# TMR_MAGSAT.net
KiCad netlist of a schematic drawn in Altium Designer
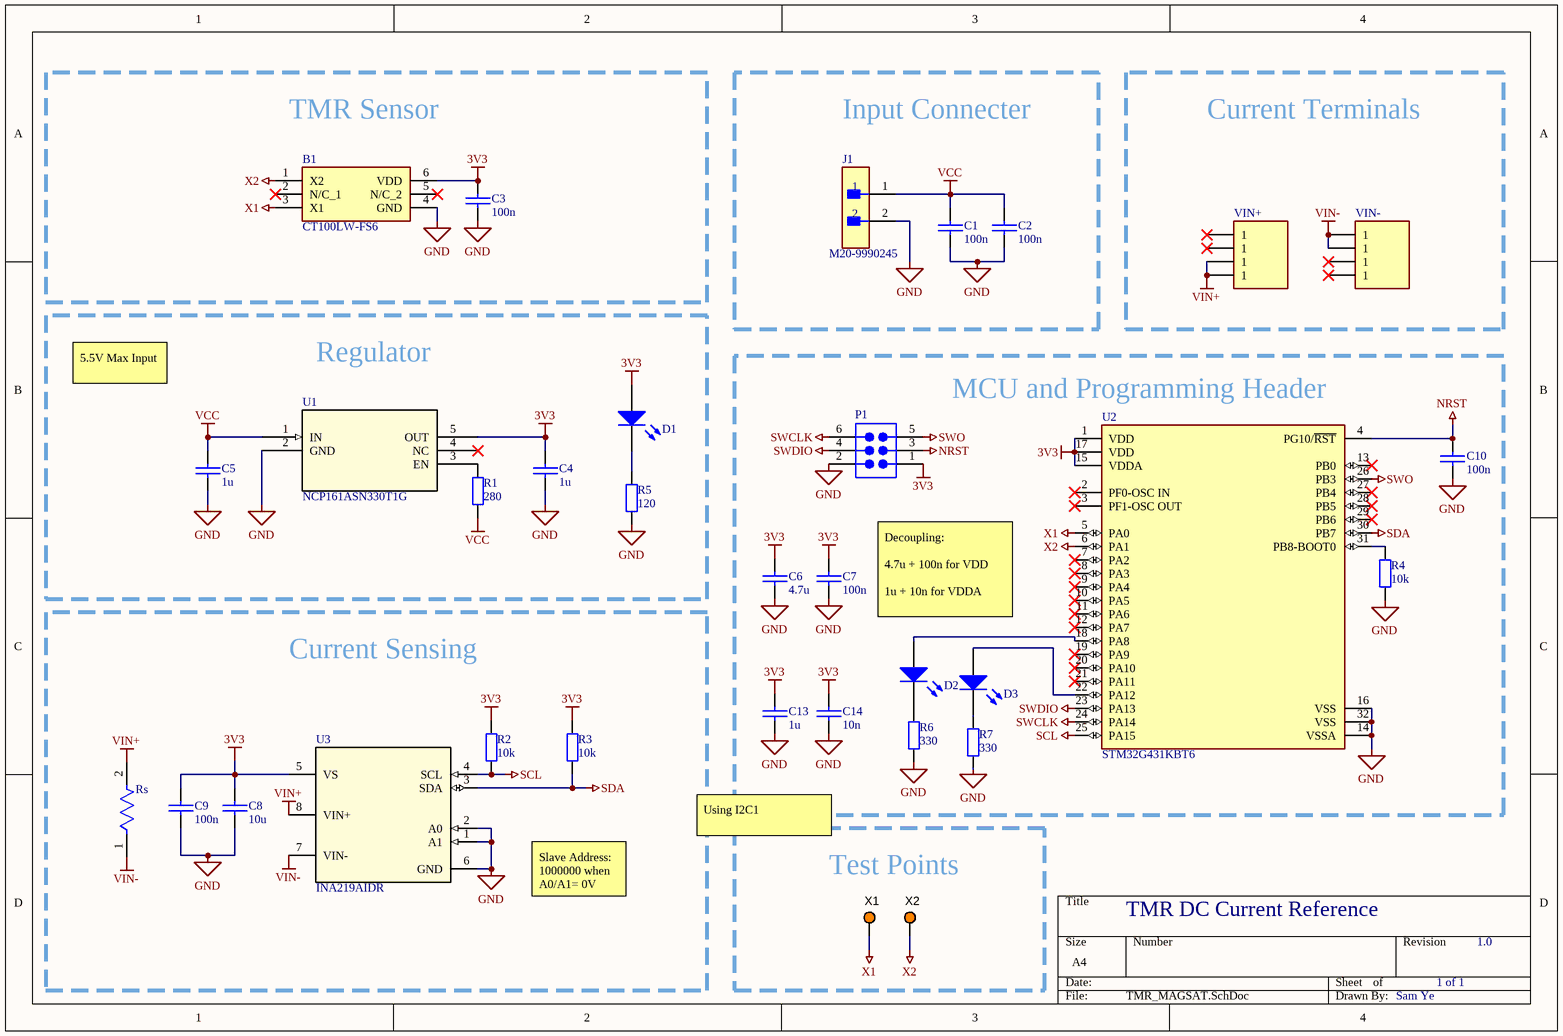
[diagram p0: TMR_MAGSAT.SchDoc]

(export (version "E")
  (design (tool "Eeschema 10.0.6"))
  (components
    (comp (ref "B1")
      (value "CT100LW-FS6")
      (footprint "SOT95P280X135-6N")
      (libsource (lib "CT100LW-FS6") (part "CT100LW-FS6"))
    )
    (comp (ref "C1")
      (value "100n")
      (footprint "0805 CAP")
      (description "SMT ceramic capacitor 0805 size")
      (libsource (lib "EE209_SchLib") (part "CerCap_SMT_0805"))
    )
    (comp (ref "C2")
      (value "100n")
      (footprint "0805 CAP")
      (description "SMT ceramic capacitor 0805 size")
      (libsource (lib "EE209_SchLib") (part "CerCap_SMT_0805"))
    )
    (comp (ref "C3")
      (value "100n")
      (footprint "0805 CAP")
      (description "SMT ceramic capacitor 0805 size")
      (libsource (lib "EE209_SchLib") (part "CerCap_SMT_0805"))
    )
    (comp (ref "C4")
      (value "1u")
      (footprint "0805 CAP")
      (description "SMT ceramic capacitor 0805 size")
      (libsource (lib "EE209_SchLib") (part "CerCap_SMT_0805"))
    )
    (comp (ref "C5")
      (value "1u")
      (footprint "0805 CAP")
      (description "SMT ceramic capacitor 0805 size")
      (libsource (lib "EE209_SchLib") (part "CerCap_SMT_0805"))
    )
    (comp (ref "C6")
      (value "4.7u")
      (footprint "0805 CAP")
      (description "SMT ceramic capacitor 0805 size")
      (libsource (lib "EE209_SchLib") (part "CerCap_SMT_0805"))
    )
    (comp (ref "C7")
      (value "100n")
      (footprint "0805 CAP")
      (description "SMT ceramic capacitor 0805 size")
      (libsource (lib "EE209_SchLib") (part "CerCap_SMT_0805"))
    )
    (comp (ref "C8")
      (value "10u")
      (footprint "0805 CAP")
      (description "SMT ceramic capacitor 0805 size")
      (libsource (lib "EE209_SchLib") (part "CerCap_SMT_0805"))
    )
    (comp (ref "C9")
      (value "100n")
      (footprint "0805 CAP")
      (description "SMT ceramic capacitor 0805 size")
      (libsource (lib "EE209_SchLib") (part "CerCap_SMT_0805"))
    )
    (comp (ref "C10")
      (value "100n")
      (footprint "0805 CAP")
      (description "SMT ceramic capacitor 0805 size")
      (libsource (lib "EE209_SchLib") (part "CerCap_SMT_0805"))
    )
    (comp (ref "C13")
      (value "1u")
      (footprint "0805 CAP")
      (description "SMT ceramic capacitor 0805 size")
      (libsource (lib "EE209_SchLib") (part "CerCap_SMT_0805"))
    )
    (comp (ref "C14")
      (value "10n")
      (footprint "0805 CAP")
      (description "SMT ceramic capacitor 0805 size")
      (libsource (lib "EE209_SchLib") (part "CerCap_SMT_0805"))
    )
    (comp (ref "D1")
      (value "LTST-C170KGKT")
      (footprint "0805 LED")
      (description "SMT LED 0805 size")
      (fields (field (name "MANUFACTURER") "Lite-On Inc."))
      (libsource (lib "EE209_SchLib") (part "LED_SMT_0805"))
    )
    (comp (ref "D2")
      (value "LTST-C170KGKT")
      (footprint "0805 LED")
      (description "SMT LED 0805 size")
      (fields (field (name "MANUFACTURER") "Lite-On Inc."))
      (libsource (lib "EE209_SchLib") (part "LED_SMT_0805"))
    )
    (comp (ref "D3")
      (value "LTST-C170KGKT")
      (footprint "0805 LED")
      (description "SMT LED 0805 size")
      (fields (field (name "MANUFACTURER") "Lite-On Inc."))
      (libsource (lib "EE209_SchLib") (part "LED_SMT_0805"))
    )
    (comp (ref "J1")
      (value "M20-9990245")
      (footprint "FP-M20-9990245-MFG")
      (description "CONN HEADER VERT 2POS 2.54MM")
      (fields (field (name "VOLTAGE") "50V"))
      (libsource (lib "male_headers") (part "CMP-15831-000105-1"))
    )
    (comp (ref "P1")
      (value "MTSW-103-07-F-D-244")
      (footprint "SMTC-MTSW-103-07-X-D-244")
      (fields (field (name "MANUFACTURER") "Samtec"))
      (libsource (lib "Altium Content Vault") (part "SMTC-MTSW-103-07-X-D-244"))
    )
    (comp (ref "R1")
      (value "280")
      (footprint "0805 RES")
      (description "0805 resistor")
      (fields (field (name "PUBLISHER") "Altium Limited"))
      (libsource (lib "EE209_SchLib") (part "Res_SMT_0805"))
    )
    (comp (ref "R2")
      (value "10k")
      (footprint "0805 RES")
      (description "0805 resistor")
      (fields (field (name "PUBLISHER") "Altium Limited"))
      (libsource (lib "EE209_SchLib") (part "Res_SMT_0805"))
    )
    (comp (ref "R3")
      (value "10k")
      (footprint "0805 RES")
      (description "0805 resistor")
      (fields (field (name "PUBLISHER") "Altium Limited"))
      (libsource (lib "EE209_SchLib") (part "Res_SMT_0805"))
    )
    (comp (ref "R4")
      (value "10k")
      (footprint "0805 RES")
      (description "0805 resistor")
      (fields (field (name "PUBLISHER") "Altium Limited"))
      (libsource (lib "EE209_SchLib") (part "Res_SMT_0805"))
    )
    (comp (ref "R5")
      (value "120")
      (footprint "0805 RES")
      (description "0805 resistor")
      (fields (field (name "PUBLISHER") "Altium Limited"))
      (libsource (lib "EE209_SchLib") (part "Res_SMT_0805"))
    )
    (comp (ref "R6")
      (value "330")
      (footprint "0805 RES")
      (description "0805 resistor")
      (fields (field (name "PUBLISHER") "Altium Limited"))
      (libsource (lib "EE209_SchLib") (part "Res_SMT_0805"))
    )
    (comp (ref "R7")
      (value "330")
      (footprint "0805 RES")
      (description "0805 resistor")
      (fields (field (name "PUBLISHER") "Altium Limited"))
      (libsource (lib "EE209_SchLib") (part "Res_SMT_0805"))
    )
    (comp (ref "Rs")
      (value "PA2512FKM7W0R001E")
      (footprint "FP-PA2512E-0R001-0R004-IPC_A")
      (description "METAL CURRENT SENSOR 2512 1% 75P")
      (fields
        (field (name "OCTOPART") "https://octopart.com/pa2512fkm7w0r001e-yageo-94661137")
        (field (name "MANUFACTURER") "Yageo")
      )
      (libsource (lib "shunt_resister_package") (part "CMP-03412-024792-1"))
    )
    (comp (ref "U1")
      (value "NCP161ASN330T1G")
      (footprint "SOT23_527AH_ONS")
      (description "Description")
      (fields (field (name "COPYRIGHT") "Copyright (C) 2026 Ultra Librarian. All rights reserved."))
      (libsource (lib "NCP161ASN330T1G") (part "NCP161ASN330T1G"))
    )
    (comp (ref "U2")
      (value "STM32G431KBT6")
      (footprint "FP-LQFP32-5V-IPC_B")
      (description "IC MCU 32BIT 128KB FLASH 32LQFP")
      (libsource (lib "Altium Content Vault") (part "c9e0a49b9ddd2147befd892ac7d673c"))
    )
    (comp (ref "U3")
      (value "INA219AIDR")
      (footprint "D0008A_N")
      (description "26-V 12-bit I2C output digital power monitor 8-SOIC -40 to 125")
      (fields
        (field (name "PARTNUMBER") "INA219BIDR")
        (field (name "ALTERNATE_PARTNUMBER") "INA219BID")
        (field (name "COPYRIGHT") "Copyright (C) 2026 Ultra Librarian. All rights reserved.")
      )
      (libsource (lib "INA219AIDR") (part "INA219AIDR"))
    )
    (comp (ref "VIN+")
      (value "7771")
      (footprint "KEYSTONE_7771")
      (description "Screw Terminal;Nickel;15 Amp;Thru-Hole;Vertical;Unassembled;PC;M3 ¦ Keystone Electronics 7771")
      (fields (field (name "MF") "Keystone Electronics"))
      (libsource (lib "7771") (part "7771"))
    )
    (comp (ref "VIN-")
      (value "7771")
      (footprint "KEYSTONE_7771")
      (description "Screw Terminal;Nickel;15 Amp;Thru-Hole;Vertical;Unassembled;PC;M3 ¦ Keystone Electronics 7771")
      (fields (field (name "MF") "Keystone Electronics"))
      (libsource (lib "7771") (part "7771"))
    )
    (comp (ref "X1")
      (value "5003")
      (footprint "EE209_PcbLib:TP_TH")
      (description "Test Point, Orange, 1-Pin THD, RoHS")
      (libsource (lib "EE209_SchLib") (part "TestPoint"))
    )
    (comp (ref "X2")
      (value "5003")
      (footprint "EE209_PcbLib:TP_TH")
      (description "Test Point, Orange, 1-Pin THD, RoHS")
      (libsource (lib "EE209_SchLib") (part "TestPoint"))
    )
  )
  (nets
    (net (code "1") (name "3V3") (class "Default")
      (node (ref "B1") (pin "6") (pinfunction "VDD_6") (pintype "passive"))
      (node (ref "C13") (pin "1") (pinfunction "1_1") (pintype "passive"))
      (node (ref "C14") (pin "1") (pinfunction "1_1") (pintype "passive"))
      (node (ref "C3") (pin "1") (pinfunction "1_1") (pintype "passive"))
      (node (ref "C4") (pin "1") (pinfunction "1_1") (pintype "passive"))
      (node (ref "C6") (pin "1") (pinfunction "1_1") (pintype "passive"))
      (node (ref "C7") (pin "1") (pinfunction "1_1") (pintype "passive"))
      (node (ref "C8") (pin "1") (pinfunction "1_1") (pintype "passive"))
      (node (ref "C9") (pin "1") (pinfunction "1_1") (pintype "passive"))
      (node (ref "D1") (pin "1") (pinfunction "A_1") (pintype "passive"))
      (node (ref "P1") (pin "1") (pinfunction "1_1") (pintype "passive"))
      (node (ref "R2") (pin "2") (pinfunction "2_2") (pintype "passive"))
      (node (ref "R3") (pin "2") (pinfunction "2_2") (pintype "passive"))
      (node (ref "U1") (pin "5") (pinfunction "OUT_5") (pintype "power_in"))
      (node (ref "U2") (pin "1") (pinfunction "VDD_1") (pintype "power_in"))
      (node (ref "U2") (pin "15") (pinfunction "VDDA_15") (pintype "power_in"))
      (node (ref "U2") (pin "17") (pinfunction "VDD_17") (pintype "power_in"))
      (node (ref "U3") (pin "5") (pinfunction "VS_5") (pintype "power_in"))
    )
    (net (code "2") (name "GND") (class "Default")
      (node (ref "B1") (pin "4") (pinfunction "GND_4") (pintype "passive"))
      (node (ref "C1") (pin "2") (pinfunction "2_2") (pintype "passive"))
      (node (ref "C10") (pin "2") (pinfunction "2_2") (pintype "passive"))
      (node (ref "C13") (pin "2") (pinfunction "2_2") (pintype "passive"))
      (node (ref "C14") (pin "2") (pinfunction "2_2") (pintype "passive"))
      (node (ref "C2") (pin "2") (pinfunction "2_2") (pintype "passive"))
      (node (ref "C3") (pin "2") (pinfunction "2_2") (pintype "passive"))
      (node (ref "C4") (pin "2") (pinfunction "2_2") (pintype "passive"))
      (node (ref "C5") (pin "2") (pinfunction "2_2") (pintype "passive"))
      (node (ref "C6") (pin "2") (pinfunction "2_2") (pintype "passive"))
      (node (ref "C7") (pin "2") (pinfunction "2_2") (pintype "passive"))
      (node (ref "C8") (pin "2") (pinfunction "2_2") (pintype "passive"))
      (node (ref "C9") (pin "2") (pinfunction "2_2") (pintype "passive"))
      (node (ref "J1") (pin "2") (pinfunction "2_2") (pintype "passive"))
      (node (ref "P1") (pin "2") (pinfunction "2_2") (pintype "passive"))
      (node (ref "R4") (pin "1") (pinfunction "1_1") (pintype "passive"))
      (node (ref "R5") (pin "1") (pinfunction "1_1") (pintype "passive"))
      (node (ref "R6") (pin "1") (pinfunction "1_1") (pintype "passive"))
      (node (ref "R7") (pin "1") (pinfunction "1_1") (pintype "passive"))
      (node (ref "U1") (pin "2") (pinfunction "GND_2") (pintype "power_in"))
      (node (ref "U2") (pin "14") (pinfunction "VSSA_14") (pintype "power_in"))
      (node (ref "U2") (pin "16") (pinfunction "VSS_16") (pintype "power_in"))
      (node (ref "U2") (pin "32") (pinfunction "VSS_32") (pintype "power_in"))
      (node (ref "U3") (pin "1") (pinfunction "A1_1") (pintype "input"))
      (node (ref "U3") (pin "2") (pinfunction "A0_2") (pintype "input"))
      (node (ref "U3") (pin "6") (pinfunction "GND_6") (pintype "power_in"))
    )
    (net (code "3") (name "NRST") (class "Default")
      (node (ref "C10") (pin "1") (pinfunction "1_1") (pintype "passive"))
      (node (ref "P1") (pin "3") (pinfunction "3_3") (pintype "passive"))
      (node (ref "U2") (pin "4") (pinfunction "PG10/~{RST}_4") (pintype "passive"))
    )
    (net (code "4") (name "Net-(D1-K)") (class "Default")
      (node (ref "D1") (pin "2") (pinfunction "K_2") (pintype "passive"))
      (node (ref "R5") (pin "2") (pinfunction "2_2") (pintype "passive"))
    )
    (net (code "5") (name "Net-(D2-A)") (class "Default")
      (node (ref "D2") (pin "1") (pinfunction "A_1") (pintype "passive"))
      (node (ref "U2") (pin "18") (pinfunction "PA8_18") (pintype "bidirectional"))
    )
    (net (code "6") (name "Net-(D2-K)") (class "Default")
      (node (ref "D2") (pin "2") (pinfunction "K_2") (pintype "passive"))
      (node (ref "R6") (pin "2") (pinfunction "2_2") (pintype "passive"))
    )
    (net (code "7") (name "Net-(D3-A)") (class "Default")
      (node (ref "D3") (pin "1") (pinfunction "A_1") (pintype "passive"))
      (node (ref "U2") (pin "22") (pinfunction "PA12_22") (pintype "bidirectional"))
    )
    (net (code "8") (name "Net-(D3-K)") (class "Default")
      (node (ref "D3") (pin "2") (pinfunction "K_2") (pintype "passive"))
      (node (ref "R7") (pin "2") (pinfunction "2_2") (pintype "passive"))
    )
    (net (code "9") (name "Net-(U1-EN)") (class "Default")
      (node (ref "R1") (pin "2") (pinfunction "2_2") (pintype "passive"))
      (node (ref "U1") (pin "3") (pinfunction "EN_3") (pintype "passive"))
    )
    (net (code "10") (name "Net-(U2-PB8-BOOT0)") (class "Default")
      (node (ref "R4") (pin "2") (pinfunction "2_2") (pintype "passive"))
      (node (ref "U2") (pin "31") (pinfunction "PB8-BOOT0_31") (pintype "bidirectional"))
    )
    (net (code "11") (name "SCL") (class "Default")
      (node (ref "R2") (pin "1") (pinfunction "1_1") (pintype "passive"))
      (node (ref "U2") (pin "25") (pinfunction "PA15_25") (pintype "bidirectional"))
      (node (ref "U3") (pin "4") (pinfunction "SCL_4") (pintype "input"))
    )
    (net (code "12") (name "SDA") (class "Default")
      (node (ref "R3") (pin "1") (pinfunction "1_1") (pintype "passive"))
      (node (ref "U2") (pin "30") (pinfunction "PB7_30") (pintype "bidirectional"))
      (node (ref "U3") (pin "3") (pinfunction "SDA_3") (pintype "bidirectional"))
    )
    (net (code "13") (name "SWCLK") (class "Default")
      (node (ref "P1") (pin "6") (pinfunction "6_6") (pintype "passive"))
      (node (ref "U2") (pin "24") (pinfunction "PA14_24") (pintype "bidirectional"))
    )
    (net (code "14") (name "SWDIO") (class "Default")
      (node (ref "P1") (pin "4") (pinfunction "4_4") (pintype "passive"))
      (node (ref "U2") (pin "23") (pinfunction "PA13_23") (pintype "bidirectional"))
    )
    (net (code "15") (name "SWO") (class "Default")
      (node (ref "P1") (pin "5") (pinfunction "5_5") (pintype "passive"))
      (node (ref "U2") (pin "26") (pinfunction "PB3_26") (pintype "bidirectional"))
    )
    (net (code "16") (name "VCC") (class "Default")
      (node (ref "C1") (pin "1") (pinfunction "1_1") (pintype "passive"))
      (node (ref "C2") (pin "1") (pinfunction "1_1") (pintype "passive"))
      (node (ref "C5") (pin "1") (pinfunction "1_1") (pintype "passive"))
      (node (ref "J1") (pin "1") (pinfunction "1_1") (pintype "passive"))
      (node (ref "R1") (pin "1") (pinfunction "1_1") (pintype "passive"))
      (node (ref "U1") (pin "1") (pinfunction "IN_1") (pintype "input"))
    )
    (net (code "17") (name "VIN+") (class "Default")
      (node (ref "Rs") (pin "2") (pinfunction "2_2") (pintype "passive"))
      (node (ref "U3") (pin "8") (pinfunction "VIN+_8") (pintype "power_in"))
      (node (ref "VIN+") (pin "1_3") (pinfunction "1_1_3") (pintype "passive"))
      (node (ref "VIN+") (pin "1_4") (pinfunction "1_1_4") (pintype "passive"))
    )
    (net (code "18") (name "VIN-") (class "Default")
      (node (ref "Rs") (pin "1") (pinfunction "1_1") (pintype "passive"))
      (node (ref "U3") (pin "7") (pinfunction "VIN-_7") (pintype "power_in"))
      (node (ref "VIN-") (pin "1_1") (pinfunction "1_1_1") (pintype "passive"))
      (node (ref "VIN-") (pin "1_2") (pinfunction "1_1_2") (pintype "passive"))
    )
    (net (code "19") (name "X1") (class "Default")
      (node (ref "B1") (pin "3") (pinfunction "X1_3") (pintype "passive"))
      (node (ref "U2") (pin "5") (pinfunction "PA0_5") (pintype "bidirectional"))
      (node (ref "X1") (pin "1") (pinfunction "1_1") (pintype "passive"))
    )
    (net (code "20") (name "X2") (class "Default")
      (node (ref "B1") (pin "1") (pinfunction "X2_1") (pintype "passive"))
      (node (ref "U2") (pin "6") (pinfunction "PA1_6") (pintype "bidirectional"))
      (node (ref "X2") (pin "1") (pinfunction "1_1") (pintype "passive"))
    )
    (net (code "21") (name "unconnected-(B1-N{slash}C_1-Pad2)") (class "Default")
      (node (ref "B1") (pin "2") (pinfunction "N/C_1_2") (pintype "passive+no_connect"))
    )
    (net (code "22") (name "unconnected-(B1-N{slash}C_2-Pad5)") (class "Default")
      (node (ref "B1") (pin "5") (pinfunction "N/C_2_5") (pintype "passive+no_connect"))
    )
    (net (code "23") (name "unconnected-(U1-NC-Pad4)") (class "Default")
      (node (ref "U1") (pin "4") (pinfunction "NC_4") (pintype "passive+no_connect"))
    )
    (net (code "24") (name "unconnected-(U2-PA2-Pad7)") (class "Default")
      (node (ref "U2") (pin "7") (pinfunction "PA2_7") (pintype "bidirectional+no_connect"))
    )
    (net (code "25") (name "unconnected-(U2-PA3-Pad8)") (class "Default")
      (node (ref "U2") (pin "8") (pinfunction "PA3_8") (pintype "bidirectional+no_connect"))
    )
    (net (code "26") (name "unconnected-(U2-PA4-Pad9)") (class "Default")
      (node (ref "U2") (pin "9") (pinfunction "PA4_9") (pintype "bidirectional+no_connect"))
    )
    (net (code "27") (name "unconnected-(U2-PA5-Pad10)") (class "Default")
      (node (ref "U2") (pin "10") (pinfunction "PA5_10") (pintype "bidirectional+no_connect"))
    )
    (net (code "28") (name "unconnected-(U2-PA6-Pad11)") (class "Default")
      (node (ref "U2") (pin "11") (pinfunction "PA6_11") (pintype "bidirectional+no_connect"))
    )
    (net (code "29") (name "unconnected-(U2-PA7-Pad12)") (class "Default")
      (node (ref "U2") (pin "12") (pinfunction "PA7_12") (pintype "bidirectional+no_connect"))
    )
    (net (code "30") (name "unconnected-(U2-PA9-Pad19)") (class "Default")
      (node (ref "U2") (pin "19") (pinfunction "PA9_19") (pintype "bidirectional+no_connect"))
    )
    (net (code "31") (name "unconnected-(U2-PA10-Pad20)") (class "Default")
      (node (ref "U2") (pin "20") (pinfunction "PA10_20") (pintype "bidirectional+no_connect"))
    )
    (net (code "32") (name "unconnected-(U2-PA11-Pad21)") (class "Default")
      (node (ref "U2") (pin "21") (pinfunction "PA11_21") (pintype "bidirectional+no_connect"))
    )
    (net (code "33") (name "unconnected-(U2-PB0-Pad13)") (class "Default")
      (node (ref "U2") (pin "13") (pinfunction "PB0_13") (pintype "bidirectional+no_connect"))
    )
    (net (code "34") (name "unconnected-(U2-PB4-Pad27)") (class "Default")
      (node (ref "U2") (pin "27") (pinfunction "PB4_27") (pintype "bidirectional+no_connect"))
    )
    (net (code "35") (name "unconnected-(U2-PB5-Pad28)") (class "Default")
      (node (ref "U2") (pin "28") (pinfunction "PB5_28") (pintype "bidirectional+no_connect"))
    )
    (net (code "36") (name "unconnected-(U2-PB6-Pad29)") (class "Default")
      (node (ref "U2") (pin "29") (pinfunction "PB6_29") (pintype "bidirectional+no_connect"))
    )
    (net (code "37") (name "unconnected-(U2-PF0-OSC_IN-Pad2)") (class "Default")
      (node (ref "U2") (pin "2") (pinfunction "PF0-OSC_IN_2") (pintype "passive+no_connect"))
    )
    (net (code "38") (name "unconnected-(U2-PF1-OSC_OUT-Pad3)") (class "Default")
      (node (ref "U2") (pin "3") (pinfunction "PF1-OSC_OUT_3") (pintype "passive+no_connect"))
    )
    (net (code "39") (name "unconnected-(VIN+-1-Pad1_1)") (class "Default")
      (node (ref "VIN+") (pin "1_1") (pinfunction "1_1_1") (pintype "passive+no_connect"))
    )
    (net (code "40") (name "unconnected-(VIN+-1-Pad1_2)") (class "Default")
      (node (ref "VIN+") (pin "1_2") (pinfunction "1_1_2") (pintype "passive+no_connect"))
    )
    (net (code "41") (name "unconnected-(VIN--1-Pad1_3)") (class "Default")
      (node (ref "VIN-") (pin "1_3") (pinfunction "1_1_3") (pintype "passive+no_connect"))
    )
    (net (code "42") (name "unconnected-(VIN--1-Pad1_4)") (class "Default")
      (node (ref "VIN-") (pin "1_4") (pinfunction "1_1_4") (pintype "passive+no_connect"))
    )
  )
)
